# gpio4s5.net
KiCad netlist of a schematic drawn in EAGLE
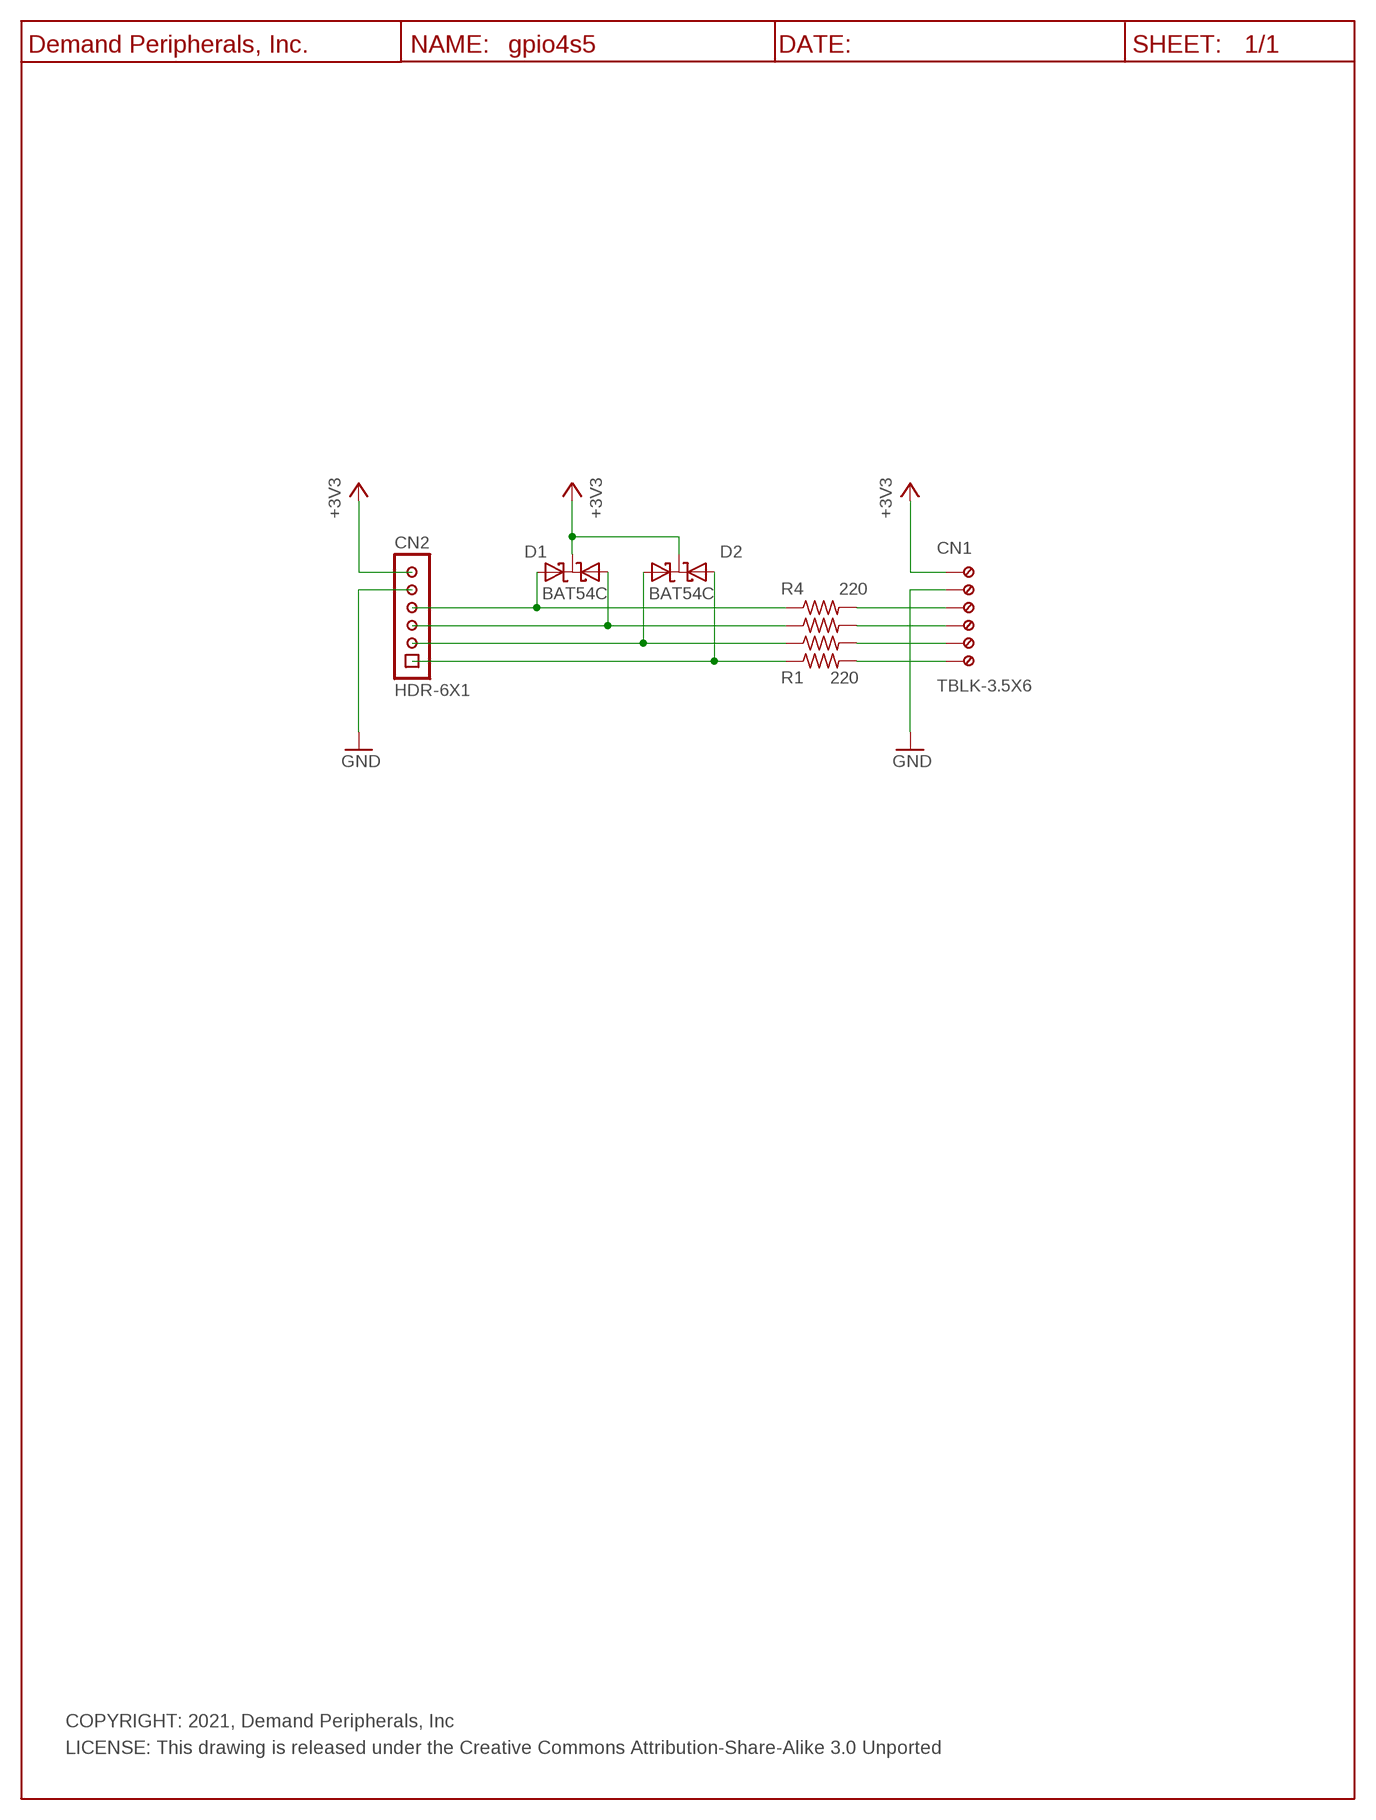
[diagram p0: schematic, sheet 1]

(export (version "E")
  (design (tool "Eeschema 10.0.6"))
  (components
    (comp (ref "CN1")
      (value "TBLK-3.5X6")
      (footprint "eagle-import:TBLK-3.5X6")
      (libsource (lib "eagle-import") (part "TBLK-3.5X6"))
    )
    (comp (ref "CN2")
      (value "HDR-6X1")
      (footprint "eagle-import:HDR-6X1")
      (libsource (lib "eagle-import") (part "HDR-6X1"))
    )
    (comp (ref "D1")
      (value "BAT54C")
      (footprint "eagle-import:SOT23")
      (libsource (lib "eagle-import") (part "BAT54C"))
    )
    (comp (ref "D2")
      (value "BAT54C")
      (footprint "eagle-import:SOT23")
      (libsource (lib "eagle-import") (part "BAT54C"))
    )
    (comp (ref "R1")
      (value "220")
      (footprint "eagle-import:R0603")
      (libsource (lib "eagle-import") (part "R220_R0603"))
    )
    (comp (ref "R2")
      (value "220")
      (footprint "eagle-import:R0603")
      (libsource (lib "eagle-import") (part "R220_R0603"))
    )
    (comp (ref "R3")
      (value "220")
      (footprint "eagle-import:R0603")
      (libsource (lib "eagle-import") (part "R220_R0603"))
    )
    (comp (ref "R4")
      (value "220")
      (footprint "eagle-import:R0603")
      (libsource (lib "eagle-import") (part "R220_R0603"))
    )
    (comp (ref "U$1")
      (value "DP_FRAME_P")
      (footprint "eagle-import:P_FRAME")
      (libsource (lib "eagle-import") (part "DP_FRAME_P"))
    )
  )
  (nets
    (net (code "1") (name "+3V3") (class "Default")
      (node (ref "CN1") (pin "1") (pinfunction "KL_1") (pintype "passive"))
      (node (ref "CN2") (pin "6") (pinfunction "6_6") (pintype "passive"))
      (node (ref "D1") (pin "3") (pinfunction "CC_3") (pintype "passive"))
      (node (ref "D2") (pin "3") (pinfunction "CC_3") (pintype "passive"))
    )
    (net (code "2") (name "GND") (class "Default")
      (node (ref "CN1") (pin "2") (pinfunction "KL1_2") (pintype "passive"))
      (node (ref "CN2") (pin "5") (pinfunction "5_5") (pintype "passive"))
    )
    (net (code "3") (name "Net-(CN1-KL2)") (class "Default")
      (node (ref "CN1") (pin "3") (pinfunction "KL2_3") (pintype "passive"))
      (node (ref "R4") (pin "2") (pinfunction "2_2") (pintype "passive"))
    )
    (net (code "4") (name "Net-(CN1-KL3)") (class "Default")
      (node (ref "CN1") (pin "4") (pinfunction "KL3_4") (pintype "passive"))
      (node (ref "R3") (pin "2") (pinfunction "2_2") (pintype "passive"))
    )
    (net (code "5") (name "Net-(CN1-KL4)") (class "Default")
      (node (ref "CN1") (pin "5") (pinfunction "KL4_5") (pintype "passive"))
      (node (ref "R2") (pin "2") (pinfunction "2_2") (pintype "passive"))
    )
    (net (code "6") (name "Net-(CN1-KL5)") (class "Default")
      (node (ref "CN1") (pin "6") (pinfunction "KL5_6") (pintype "passive"))
      (node (ref "R1") (pin "2") (pinfunction "2_2") (pintype "passive"))
    )
    (net (code "7") (name "Net-(D1-A)") (class "Default")
      (node (ref "CN2") (pin "3") (pinfunction "3_3") (pintype "passive"))
      (node (ref "D1") (pin "2") (pinfunction "A_2") (pintype "passive"))
      (node (ref "R3") (pin "1") (pinfunction "1_1") (pintype "passive"))
    )
    (net (code "8") (name "Net-(D1-A1)") (class "Default")
      (node (ref "CN2") (pin "4") (pinfunction "4_4") (pintype "passive"))
      (node (ref "D1") (pin "1") (pinfunction "A1_1") (pintype "passive"))
      (node (ref "R4") (pin "1") (pinfunction "1_1") (pintype "passive"))
    )
    (net (code "9") (name "Net-(D2-A)") (class "Default")
      (node (ref "CN2") (pin "1") (pinfunction "1_1") (pintype "passive"))
      (node (ref "D2") (pin "2") (pinfunction "A_2") (pintype "passive"))
      (node (ref "R1") (pin "1") (pinfunction "1_1") (pintype "passive"))
    )
    (net (code "10") (name "Net-(D2-A1)") (class "Default")
      (node (ref "CN2") (pin "2") (pinfunction "2_2") (pintype "passive"))
      (node (ref "D2") (pin "1") (pinfunction "A1_1") (pintype "passive"))
      (node (ref "R2") (pin "1") (pinfunction "1_1") (pintype "passive"))
    )
  )
)
